# conn_usbc.net
KiCad netlist of a schematic drawn in Altium Designer
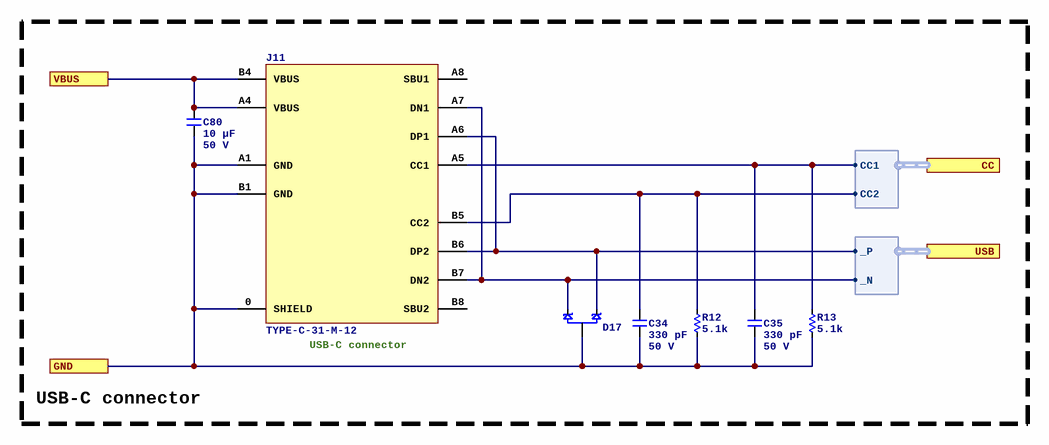
[diagram p0: conn_usbc.SchDoc]

(export (version "E")
  (design (tool "Eeschema 10.0.6"))
  (components
    (comp (ref "C34")
      (value "CL05C331JB5NNNC")
      (footprint "C0402")
      (fields
        (field (name "CAPACITANCE") "330 pF")
        (field (name "MANUFACTURER") "Samsung Electro-Mechanics")
        (field (name "VOLTAGE RATING") "50 V")
      )
      (libsource (lib "database") (part "__template_cap"))
    )
    (comp (ref "C35")
      (value "CL05C331JB5NNNC")
      (footprint "C0402")
      (fields
        (field (name "CAPACITANCE") "330 pF")
        (field (name "MANUFACTURER") "Samsung Electro-Mechanics")
        (field (name "VOLTAGE RATING") "50 V")
      )
      (libsource (lib "database") (part "__template_cap"))
    )
    (comp (ref "C80")
      (value "CL31B106KBHNNNE")
      (footprint "C1206")
      (fields
        (field (name "CAPACITANCE") "10 µF")
        (field (name "MANUFACTURER") "Samsung Electro-Mechanics")
        (field (name "VOLTAGE RATING") "50 V")
      )
      (libsource (lib "database") (part "__template_cap"))
    )
    (comp (ref "D17")
      (value "PESD2USB3UX")
      (footprint "3SOT23")
      (description "DIODE ESD USB SOT-23")
      (fields (field (name "MANUFACTURER") "Nexperia USA Inc."))
      (libsource (lib "database") (part "PESD2USB3UX"))
    )
    (comp (ref "J11")
      (value "TYPE-C-31-M-12")
      (footprint "CONN_USBC_TYPE-C-31-M-12")
      (description "5A 1 16P Female Type-C SMD USB Connectors ROHS")
      (fields (field (name "MANUFACTURER") "HRO Electronics"))
      (libsource (lib "database") (part "TYPE-C-31-M-12"))
    )
    (comp (ref "R12")
      (value "5.1k")
      (footprint "R0402")
      (fields
        (field (name "TOLERANCE") "1%")
        (field (name "MANUFACTURER PART NUMBER") "0402WGF5101TCE")
        (field (name "MANUFACTURER") "UNI-ROYAL(Uniroyal Elec)")
      )
      (libsource (lib "database") (part "__template_resistor"))
    )
    (comp (ref "R13")
      (value "5.1k")
      (footprint "R0402")
      (fields
        (field (name "TOLERANCE") "1%")
        (field (name "MANUFACTURER PART NUMBER") "0402WGF5101TCE")
        (field (name "MANUFACTURER") "UNI-ROYAL(Uniroyal Elec)")
      )
      (libsource (lib "database") (part "__template_resistor"))
    )
  )
  (nets
    (net (code "3") (name "/GND") (class "Default")
      (node (ref "C34") (pin "2") (pintype "passive"))
      (node (ref "C35") (pin "2") (pintype "passive"))
      (node (ref "C80") (pin "2") (pintype "passive"))
      (node (ref "D17") (pin "3") (pintype "passive"))
      (node (ref "J11") (pin "0") (pinfunction "SHIELD_0") (pintype "power_in"))
      (node (ref "J11") (pin "A1") (pinfunction "GND_A1") (pintype "power_in"))
      (node (ref "J11") (pin "B1") (pinfunction "GND_B1") (pintype "power_in"))
      (node (ref "R12") (pin "2") (pintype "passive"))
      (node (ref "R13") (pin "2") (pintype "passive"))
    )
    (net (code "4") (name "/VBUS") (class "Default")
      (node (ref "C80") (pin "1") (pintype "passive"))
      (node (ref "J11") (pin "A4") (pinfunction "VBUS_A4") (pintype "power_in"))
      (node (ref "J11") (pin "B4") (pinfunction "VBUS_B4") (pintype "passive"))
    )
    (net (code "7") (name "Net-(J11-CC1)") (class "Default")
      (node (ref "C35") (pin "1") (pintype "passive"))
      (node (ref "J11") (pin "A5") (pinfunction "CC1_A5") (pintype "passive"))
      (node (ref "R13") (pin "1") (pintype "passive"))
    )
    (net (code "8") (name "Net-(J11-CC2)") (class "Default")
      (node (ref "C34") (pin "1") (pintype "passive"))
      (node (ref "J11") (pin "B5") (pinfunction "CC2_B5") (pintype "passive"))
      (node (ref "R12") (pin "1") (pintype "passive"))
    )
    (net (code "9") (name "Net-(J11-DN1)") (class "Default")
      (node (ref "D17") (pin "2") (pintype "passive"))
      (node (ref "J11") (pin "A7") (pinfunction "DN1_A7") (pintype "passive"))
      (node (ref "J11") (pin "B7") (pinfunction "DN2_B7") (pintype "passive"))
    )
    (net (code "10") (name "Net-(J11-DP1)") (class "Default")
      (node (ref "D17") (pin "1") (pintype "passive"))
      (node (ref "J11") (pin "A6") (pinfunction "DP1_A6") (pintype "passive"))
      (node (ref "J11") (pin "B6") (pinfunction "DP2_B6") (pintype "passive"))
    )
    (net (code "11") (name "unconnected-(J11-SBU1-PadA8)") (class "Default")
      (node (ref "J11") (pin "A8") (pinfunction "SBU1_A8") (pintype "passive"))
    )
    (net (code "12") (name "unconnected-(J11-SBU2-PadB8)") (class "Default")
      (node (ref "J11") (pin "B8") (pinfunction "SBU2_B8") (pintype "passive"))
    )
  )
)
